# buzzer_single_layer.net
KiCad netlist of a schematic drawn in EAGLE
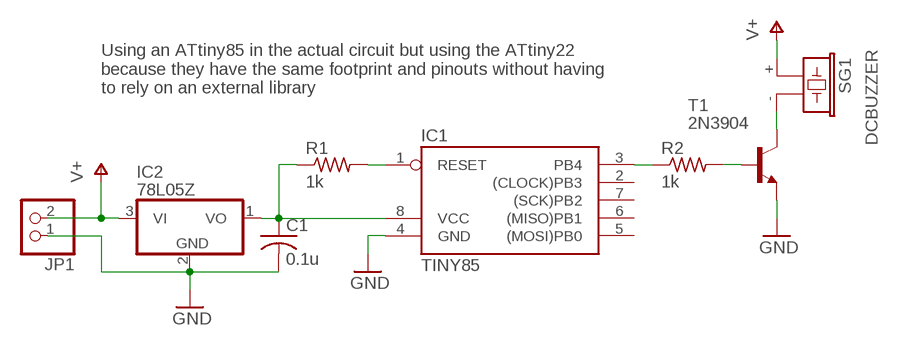
[diagram p0: schematic, sheet 1]

(export (version "E")
  (design (tool "Eeschema 10.0.6"))
  (components
    (comp (ref "C1")
      (value "0.1u")
      (footprint "eagle-import:C025-050X050")
      (libsource (lib "eagle-import") (part "C-US025-050X050"))
    )
    (comp (ref "IC1")
      (value "TINY85")
      (footprint "eagle-import:DIL08")
      (libsource (lib "eagle-import") (part "TINY22P"))
    )
    (comp (ref "IC2")
      (value "78L05Z")
      (footprint "eagle-import:TO92")
      (libsource (lib "eagle-import") (part "78ZL05"))
    )
    (comp (ref "JP1")
      (value "PINHD-1X2")
      (footprint "eagle-import:1X02")
      (libsource (lib "eagle-import") (part "PINHD-1X2"))
    )
    (comp (ref "R1")
      (value "1k")
      (footprint "eagle-import:0204_7")
      (libsource (lib "eagle-import") (part "R-US_0204/7"))
    )
    (comp (ref "R2")
      (value "1k")
      (footprint "eagle-import:0204_7")
      (libsource (lib "eagle-import") (part "R-US_0204/7"))
    )
    (comp (ref "SG1")
      (value "DCBUZZER")
      (footprint "eagle-import:F_CM12P")
      (libsource (lib "eagle-import") (part "F/CM12P"))
    )
    (comp (ref "T1")
      (value "2N3904")
      (footprint "eagle-import:TO92")
      (libsource (lib "eagle-import") (part "2N3904"))
    )
  )
  (nets
    (net (code "1") (name "GND") (class "Default")
      (node (ref "C1") (pin "2") (pinfunction "2_2") (pintype "passive"))
      (node (ref "IC1") (pin "4") (pinfunction "GND_4") (pintype "power_in"))
      (node (ref "IC2") (pin "2") (pinfunction "GND_2") (pintype "passive"))
      (node (ref "JP1") (pin "1") (pinfunction "1_1") (pintype "passive"))
      (node (ref "T1") (pin "3") (pinfunction "E_3") (pintype "passive"))
    )
    (net (code "2") (name "Net-(IC1-PB4)") (class "Default")
      (node (ref "IC1") (pin "3") (pinfunction "PB4_3") (pintype "bidirectional"))
      (node (ref "R2") (pin "1") (pinfunction "1_1") (pintype "passive"))
    )
    (net (code "3") (name "Net-(IC1-RESET)") (class "Default")
      (node (ref "IC1") (pin "1") (pinfunction "RESET_1") (pintype "input"))
      (node (ref "R1") (pin "2") (pinfunction "2_2") (pintype "passive"))
    )
    (net (code "4") (name "Net-(IC1-VCC)") (class "Default")
      (node (ref "C1") (pin "1") (pinfunction "1_1") (pintype "passive"))
      (node (ref "IC1") (pin "8") (pinfunction "VCC_8") (pintype "power_in"))
      (node (ref "IC2") (pin "1") (pinfunction "VO_1") (pintype "passive"))
      (node (ref "R1") (pin "1") (pinfunction "1_1") (pintype "passive"))
    )
    (net (code "5") (name "Net-(SG1-2)") (class "Default")
      (node (ref "SG1") (pin "-") (pinfunction "2_-") (pintype "passive"))
      (node (ref "T1") (pin "1") (pinfunction "C_1") (pintype "passive"))
    )
    (net (code "6") (name "Net-(T1-B)") (class "Default")
      (node (ref "R2") (pin "2") (pinfunction "2_2") (pintype "passive"))
      (node (ref "T1") (pin "2") (pinfunction "B_2") (pintype "passive"))
    )
    (net (code "7") (name "V+") (class "Default")
      (node (ref "IC2") (pin "3") (pinfunction "VI_3") (pintype "input"))
      (node (ref "JP1") (pin "2") (pinfunction "2_2") (pintype "passive"))
      (node (ref "SG1") (pin "+") (pinfunction "1_+") (pintype "passive"))
    )
    (net (code "8") (name "unconnected-(IC1-(CLOCK)PB3-Pad2)") (class "Default")
      (node (ref "IC1") (pin "2") (pinfunction "(CLOCK)PB3_2") (pintype "bidirectional"))
    )
    (net (code "9") (name "unconnected-(IC1-(MISO)PB1-Pad6)") (class "Default")
      (node (ref "IC1") (pin "6") (pinfunction "(MISO)PB1_6") (pintype "bidirectional"))
    )
    (net (code "10") (name "unconnected-(IC1-(MOSI)PB0-Pad5)") (class "Default")
      (node (ref "IC1") (pin "5") (pinfunction "(MOSI)PB0_5") (pintype "bidirectional"))
    )
    (net (code "11") (name "unconnected-(IC1-(SCK)PB2-Pad7)") (class "Default")
      (node (ref "IC1") (pin "7") (pinfunction "(SCK)PB2_7") (pintype "bidirectional"))
    )
  )
)
